# AD603_AGC.net
KiCad netlist of a schematic drawn in Altium Designer
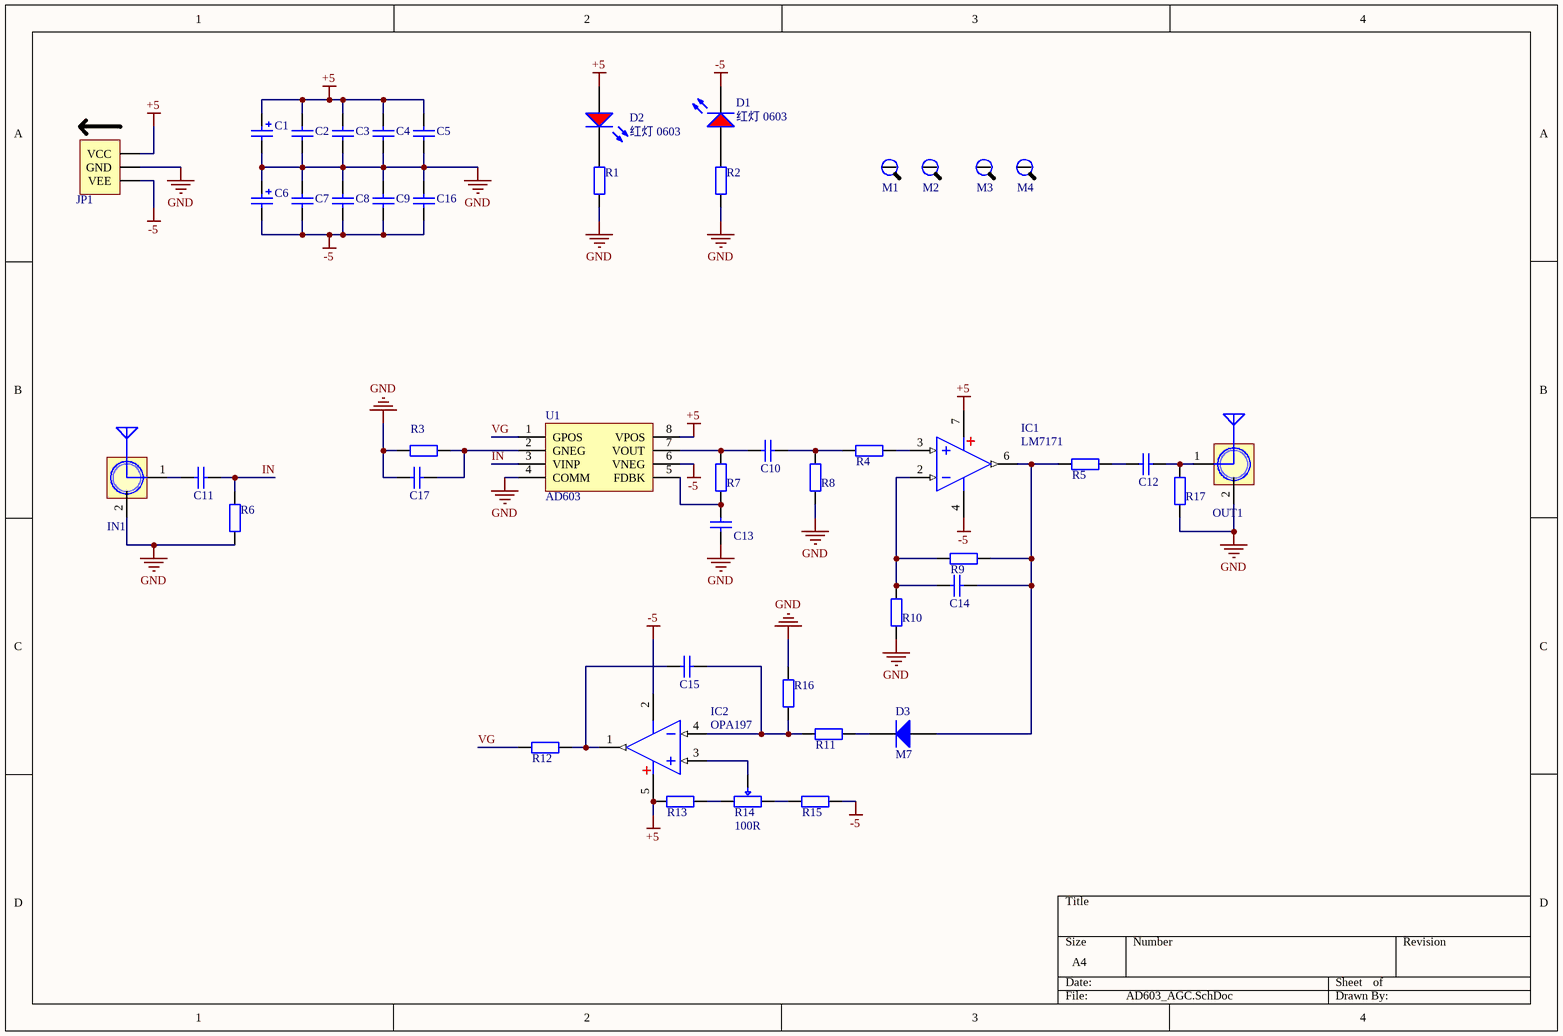
[diagram p0: AD603_AGC.SchDoc]

(export (version "E")
  (design (tool "Eeschema 10.0.6"))
  (components
    (comp (ref "C1")
      (value "10uF (106) ±10% 16V")
      (footprint "CASE-A_3216")
      (description "钽电容")
      (libsource (lib "JLC") (part "3216 10uF (106) 10% 16V"))
    )
    (comp (ref "C2")
      (value "100nF (104) 10% 50V")
      (footprint "0603_C")
      (description "贴片电容")
      (libsource (lib "JLC") (part "0603 100nF (104) 10% 50V"))
    )
    (comp (ref "C3")
      (value "100nF (104) 10% 50V")
      (footprint "0603_C")
      (description "贴片电容")
      (libsource (lib "JLC") (part "0603 100nF (104) 10% 50V"))
    )
    (comp (ref "C4")
      (value "100nF (104) 10% 50V")
      (footprint "0603_C")
      (description "贴片电容")
      (libsource (lib "JLC") (part "0603 100nF (104) 10% 50V"))
    )
    (comp (ref "C5")
      (value "100nF (104) 10% 50V")
      (footprint "0603_C")
      (description "贴片电容")
      (libsource (lib "JLC") (part "0603 100nF (104) 10% 50V"))
    )
    (comp (ref "C6")
      (value "10uF (106) ±10% 16V")
      (footprint "CASE-A_3216")
      (description "钽电容")
      (libsource (lib "JLC") (part "3216 10uF (106) 10% 16V"))
    )
    (comp (ref "C7")
      (value "100nF (104) 10% 50V")
      (footprint "0603_C")
      (description "贴片电容")
      (libsource (lib "JLC") (part "0603 100nF (104) 10% 50V"))
    )
    (comp (ref "C8")
      (value "100nF (104) 10% 50V")
      (footprint "0603_C")
      (description "贴片电容")
      (libsource (lib "JLC") (part "0603 100nF (104) 10% 50V"))
    )
    (comp (ref "C9")
      (value "100nF (104) 10% 50V")
      (footprint "0603_C")
      (description "贴片电容")
      (libsource (lib "JLC") (part "0603 100nF (104) 10% 50V"))
    )
    (comp (ref "C10")
      (value "100nF (104) 10% 50V")
      (footprint "0603_C")
      (description "贴片电容")
      (libsource (lib "JLC") (part "0603 100nF (104) 10% 50V"))
    )
    (comp (ref "C11")
      (value "100nF (104) 10% 50V")
      (footprint "0603_C")
      (description "贴片电容")
      (libsource (lib "JLC") (part "0603 100nF (104) 10% 50V"))
    )
    (comp (ref "C12")
      (value "100nF (104) 10% 50V")
      (footprint "0603_C")
      (description "贴片电容")
      (libsource (lib "JLC") (part "0603 100nF (104) 10% 50V"))
    )
    (comp (ref "C13")
      (value "100nF (104) 10% 50V")
      (footprint "0603_C")
      (description "贴片电容")
      (libsource (lib "JLC") (part "0603 100nF (104) 10% 50V"))
    )
    (comp (ref "C14")
      (value "100nF (104) 10% 50V")
      (footprint "0603_C")
      (description "贴片电容")
      (libsource (lib "JLC") (part "0603 100nF (104) 10% 50V"))
    )
    (comp (ref "C15")
      (value "100nF (104) 10% 50V")
      (footprint "0603_C")
      (description "贴片电容")
      (libsource (lib "JLC") (part "0603 100nF (104) 10% 50V"))
    )
    (comp (ref "C16")
      (value "100nF (104) 10% 50V")
      (footprint "0603_C")
      (description "贴片电容")
      (libsource (lib "JLC") (part "0603 100nF (104) 10% 50V"))
    )
    (comp (ref "C17")
      (value "100nF (104) 10% 50V")
      (footprint "0603_C")
      (description "贴片电容")
      (libsource (lib "JLC") (part "0603 100nF (104) 10% 50V"))
    )
    (comp (ref "D1")
      (value "红灯 0603")
      (footprint "0603_LED_S1")
      (description "发光二极管")
      (libsource (lib "JLC") (part "0603 红灯"))
    )
    (comp (ref "D2")
      (value "红灯 0603")
      (footprint "0603_LED_S1")
      (description "发光二极管")
      (libsource (lib "JLC") (part "0603 红灯"))
    )
    (comp (ref "D3")
      (value "M7")
      (footprint "SMA(DO-214AC)_S1")
      (description "二极管")
      (libsource (lib "JLC") (part "SMA(DO-214AC) M7"))
    )
    (comp (ref "IC1")
      (value "LM7171")
      (footprint "SOP8_N")
      (description "SOP8_轨至轨运放")
      (fields (field (name "版权归属") "源创客"))
      (libsource (lib "1.5   - 运放-功放") (part "SGM8521-8Pin"))
    )
    (comp (ref "IC2")
      (value "OPA197")
      (footprint "SOT23-5N")
      (description "SOT23-5_轨至轨运放")
      (fields (field (name "版权归属") "源创客"))
      (libsource (lib "1.5   - 运放-功放") (part "SGM8521-5Pin"))
    )
    (comp (ref "IN1")
      (value "SMA WIFI 天线接口")
      (footprint "SMA")
      (description "SMA-2.4G射频天线接口")
      (fields (field (name "版权归属") "源创客"))
      (libsource (lib "") (part "PORT_SMA_1"))
    )
    (comp (ref "JP1")
      (value "HDR-1X3")
      (footprint "Power_IN_3.81-3P")
      (description "3P接插件,模块双电源供电口")
      (fields (field (name "版权归属") "源创客"))
      (libsource (lib "Cooperation") (part "PORT_Power_IN3"))
    )
    (comp (ref "M1")
      (value "M3")
      (footprint "M3x10_L")
      (description "螺丝")
      (libsource (lib "Cooperation") (part "ELSE_M3_screw"))
    )
    (comp (ref "M2")
      (value "M3")
      (footprint "M3x10_L")
      (description "螺丝")
      (libsource (lib "Cooperation") (part "ELSE_M3_screw"))
    )
    (comp (ref "M3")
      (value "M3")
      (footprint "M3x10_L")
      (description "螺丝")
      (libsource (lib "Cooperation") (part "ELSE_M3_screw"))
    )
    (comp (ref "M4")
      (value "M3")
      (footprint "M3x10_L")
      (description "螺丝")
      (libsource (lib "Cooperation") (part "ELSE_M3_screw"))
    )
    (comp (ref "OUT1")
      (value "SMA WIFI 天线接口")
      (footprint "SMA")
      (description "SMA-2.4G射频天线接口")
      (fields (field (name "版权归属") "源创客"))
      (libsource (lib "Cooperation") (part "PORT_SMA"))
    )
    (comp (ref "R1")
      (value "10KΩ (1002) ±1%")
      (footprint "0603_R")
      (description "贴片电阻")
      (libsource (lib "") (part "0603 10KΩ (1002) 1%_1"))
    )
    (comp (ref "R2")
      (value "10KΩ (1002) ±1%")
      (footprint "0603_R")
      (description "贴片电阻")
      (libsource (lib "") (part "0603 10KΩ (1002) 1%_1"))
    )
    (comp (ref "R3")
      (value "10KΩ (1002) ±1%")
      (footprint "0603_R")
      (description "贴片电阻")
      (libsource (lib "") (part "0603 10KΩ (1002) 1%_3"))
    )
    (comp (ref "R4")
      (value "10KΩ (1002) ±1%")
      (footprint "0603_R")
      (description "贴片电阻")
      (libsource (lib "") (part "0603 10KΩ (1002) 1%_2"))
    )
    (comp (ref "R5")
      (value "10KΩ (1002) ±1%")
      (footprint "0603_R")
      (description "贴片电阻")
      (libsource (lib "") (part "0603 10KΩ (1002) 1%_2"))
    )
    (comp (ref "R6")
      (value "10KΩ (1002) ±1%")
      (footprint "0603_R")
      (description "贴片电阻")
      (libsource (lib "") (part "0603 10KΩ (1002) 1%_1"))
    )
    (comp (ref "R7")
      (value "10KΩ (1002) ±1%")
      (footprint "0603_R")
      (description "贴片电阻")
      (libsource (lib "JLC") (part "0603 10KΩ (1002) 1%"))
    )
    (comp (ref "R8")
      (value "10KΩ (1002) ±1%")
      (footprint "0603_R")
      (description "贴片电阻")
      (libsource (lib "JLC") (part "0603 10KΩ (1002) 1%"))
    )
    (comp (ref "R9")
      (value "10KΩ (1002) ±1%")
      (footprint "0603_R")
      (description "贴片电阻")
      (libsource (lib "") (part "0603 10KΩ (1002) 1%_2"))
    )
    (comp (ref "R10")
      (value "10KΩ (1002) ±1%")
      (footprint "0603_R")
      (description "贴片电阻")
      (libsource (lib "JLC") (part "0603 10KΩ (1002) 1%"))
    )
    (comp (ref "R11")
      (value "10KΩ (1002) ±1%")
      (footprint "0603_R")
      (description "贴片电阻")
      (libsource (lib "") (part "0603 10KΩ (1002) 1%_2"))
    )
    (comp (ref "R12")
      (value "10KΩ (1002) ±1%")
      (footprint "0603_R")
      (description "贴片电阻")
      (libsource (lib "") (part "0603 10KΩ (1002) 1%_2"))
    )
    (comp (ref "R13")
      (value "10KΩ (1002) ±1%")
      (footprint "0603_R")
      (description "贴片电阻")
      (libsource (lib "") (part "0603 10KΩ (1002) 1%_2"))
    )
    (comp (ref "R14")
      (value "100R")
      (footprint "adjustable resistor")
      (description "adjustable resistor可调电阻")
      (fields (field (name "Comment") "Ω"))
      (libsource (lib "Cooperation") (part "RES_Adjustable_Resistor"))
    )
    (comp (ref "R15")
      (value "10KΩ (1002) ±1%")
      (footprint "0603_R")
      (description "贴片电阻")
      (libsource (lib "") (part "0603 10KΩ (1002) 1%_2"))
    )
    (comp (ref "R16")
      (value "10KΩ (1002) ±1%")
      (footprint "0603_R")
      (description "贴片电阻")
      (libsource (lib "") (part "0603 10KΩ (1002) 1%_1"))
    )
    (comp (ref "R17")
      (value "10KΩ (1002) ±1%")
      (footprint "0603_R")
      (description "贴片电阻")
      (libsource (lib "") (part "0603 10KΩ (1002) 1%_1"))
    )
    (comp (ref "U1") (value "AD603") (footprint "SO-8") (libsource (lib "Cooperation") (part "AD603")))
  )
  (nets
    (net (code "1") (name "+5") (class "Default")
      (node (ref "C1") (pin "1") (pinfunction "1_1") (pintype "passive"))
      (node (ref "C2") (pin "2") (pinfunction "2_2") (pintype "passive"))
      (node (ref "C3") (pin "2") (pinfunction "2_2") (pintype "passive"))
      (node (ref "C4") (pin "2") (pinfunction "2_2") (pintype "passive"))
      (node (ref "C5") (pin "2") (pinfunction "2_2") (pintype "passive"))
      (node (ref "D2") (pin "A") (pinfunction "A_A") (pintype "passive"))
      (node (ref "IC1") (pin "7") (pinfunction "V+_7") (pintype "power_in"))
      (node (ref "IC2") (pin "5") (pinfunction "V+_5") (pintype "power_in"))
      (node (ref "JP1") (pin "1") (pinfunction "VCC_1") (pintype "passive"))
      (node (ref "R13") (pin "1") (pinfunction "1_1") (pintype "passive"))
      (node (ref "U1") (pin "8") (pinfunction "VPOS_8") (pintype "passive"))
    )
    (net (code "2") (name "-5") (class "Default")
      (node (ref "C16") (pin "1") (pinfunction "1_1") (pintype "passive"))
      (node (ref "C6") (pin "2") (pinfunction "2_2") (pintype "passive"))
      (node (ref "C7") (pin "1") (pinfunction "1_1") (pintype "passive"))
      (node (ref "C8") (pin "1") (pinfunction "1_1") (pintype "passive"))
      (node (ref "C9") (pin "1") (pinfunction "1_1") (pintype "passive"))
      (node (ref "D1") (pin "K") (pinfunction "K_K") (pintype "passive"))
      (node (ref "IC1") (pin "4") (pinfunction "V-_4") (pintype "power_in"))
      (node (ref "IC2") (pin "2") (pinfunction "V-_2") (pintype "power_in"))
      (node (ref "JP1") (pin "3") (pinfunction "VEE_3") (pintype "passive"))
      (node (ref "R15") (pin "2") (pinfunction "2_2") (pintype "passive"))
      (node (ref "U1") (pin "6") (pinfunction "VNEG_6") (pintype "passive"))
    )
    (net (code "3") (name "/IN") (class "Default")
      (node (ref "C11") (pin "1") (pinfunction "1_1") (pintype "passive"))
      (node (ref "R6") (pin "2") (pinfunction "2_2") (pintype "passive"))
      (node (ref "U1") (pin "3") (pinfunction "VINP_3") (pintype "passive"))
    )
    (net (code "4") (name "/VG") (class "Default")
      (node (ref "R12") (pin "1") (pinfunction "1_1") (pintype "passive"))
      (node (ref "U1") (pin "1") (pinfunction "GPOS_1") (pintype "passive"))
    )
    (net (code "5") (name "GND") (class "Default")
      (node (ref "C1") (pin "2") (pinfunction "2_2") (pintype "passive"))
      (node (ref "C13") (pin "2") (pinfunction "2_2") (pintype "passive"))
      (node (ref "C16") (pin "2") (pinfunction "2_2") (pintype "passive"))
      (node (ref "C17") (pin "2") (pinfunction "2_2") (pintype "passive"))
      (node (ref "C2") (pin "1") (pinfunction "1_1") (pintype "passive"))
      (node (ref "C3") (pin "1") (pinfunction "1_1") (pintype "passive"))
      (node (ref "C4") (pin "1") (pinfunction "1_1") (pintype "passive"))
      (node (ref "C5") (pin "1") (pinfunction "1_1") (pintype "passive"))
      (node (ref "C6") (pin "1") (pinfunction "1_1") (pintype "passive"))
      (node (ref "C7") (pin "2") (pinfunction "2_2") (pintype "passive"))
      (node (ref "C8") (pin "2") (pinfunction "2_2") (pintype "passive"))
      (node (ref "C9") (pin "2") (pinfunction "2_2") (pintype "passive"))
      (node (ref "IN1") (pin "2") (pinfunction "2_2") (pintype "passive"))
      (node (ref "JP1") (pin "2") (pinfunction "GND_2") (pintype "passive"))
      (node (ref "OUT1") (pin "2") (pinfunction "2_2") (pintype "passive"))
      (node (ref "R1") (pin "1") (pinfunction "1_1") (pintype "passive"))
      (node (ref "R10") (pin "2") (pinfunction "2_2") (pintype "passive"))
      (node (ref "R16") (pin "2") (pinfunction "2_2") (pintype "passive"))
      (node (ref "R17") (pin "1") (pinfunction "1_1") (pintype "passive"))
      (node (ref "R2") (pin "1") (pinfunction "1_1") (pintype "passive"))
      (node (ref "R3") (pin "2") (pinfunction "2_2") (pintype "passive"))
      (node (ref "R6") (pin "1") (pinfunction "1_1") (pintype "passive"))
      (node (ref "R8") (pin "2") (pinfunction "2_2") (pintype "passive"))
      (node (ref "U1") (pin "4") (pinfunction "COMM_4") (pintype "passive"))
    )
    (net (code "6") (name "Net-(C10-Pad1)") (class "Default")
      (node (ref "C10") (pin "1") (pinfunction "1_1") (pintype "passive"))
      (node (ref "R4") (pin "1") (pinfunction "1_1") (pintype "passive"))
      (node (ref "R8") (pin "1") (pinfunction "1_1") (pintype "passive"))
    )
    (net (code "7") (name "Net-(C12-Pad2)") (class "Default")
      (node (ref "C12") (pin "2") (pinfunction "2_2") (pintype "passive"))
      (node (ref "R5") (pin "2") (pinfunction "2_2") (pintype "passive"))
    )
    (net (code "8") (name "Net-(D1-PadA)") (class "Default")
      (node (ref "D1") (pin "A") (pinfunction "A_A") (pintype "passive"))
      (node (ref "R2") (pin "2") (pinfunction "2_2") (pintype "passive"))
    )
    (net (code "9") (name "Net-(D2-PadK)") (class "Default")
      (node (ref "D2") (pin "K") (pinfunction "K_K") (pintype "passive"))
      (node (ref "R1") (pin "2") (pinfunction "2_2") (pintype "passive"))
    )
    (net (code "10") (name "Net-(D3-A)") (class "Default")
      (node (ref "C14") (pin "1") (pinfunction "1_1") (pintype "passive"))
      (node (ref "D3") (pin "1") (pinfunction "A_1") (pintype "passive"))
      (node (ref "IC1") (pin "6") (pinfunction "OUT_6") (pintype "output"))
      (node (ref "R5") (pin "1") (pinfunction "1_1") (pintype "passive"))
      (node (ref "R9") (pin "2") (pinfunction "2_2") (pintype "passive"))
    )
    (net (code "11") (name "Net-(D3-K)") (class "Default")
      (node (ref "D3") (pin "2") (pinfunction "K_2") (pintype "passive"))
      (node (ref "R11") (pin "2") (pinfunction "2_2") (pintype "passive"))
    )
    (net (code "12") (name "Net-(IC1-IN-)") (class "Default")
      (node (ref "C14") (pin "2") (pinfunction "2_2") (pintype "passive"))
      (node (ref "IC1") (pin "2") (pinfunction "IN-_2") (pintype "input"))
      (node (ref "R10") (pin "1") (pinfunction "1_1") (pintype "passive"))
      (node (ref "R9") (pin "1") (pinfunction "1_1") (pintype "passive"))
    )
    (net (code "13") (name "Net-(IC1-Pad3)") (class "Default")
      (node (ref "IC1") (pin "3") (pinfunction "3_3") (pintype "input"))
      (node (ref "R4") (pin "2") (pinfunction "2_2") (pintype "passive"))
    )
    (net (code "14") (name "Net-(IC2-IN+)") (class "Default")
      (node (ref "IC2") (pin "3") (pinfunction "IN+_3") (pintype "input"))
      (node (ref "R14") (pin "2") (pinfunction "2_2") (pintype "passive"))
    )
    (net (code "15") (name "Net-(IC2-IN-)") (class "Default")
      (node (ref "C15") (pin "1") (pinfunction "1_1") (pintype "passive"))
      (node (ref "IC2") (pin "4") (pinfunction "IN-_4") (pintype "input"))
      (node (ref "R11") (pin "1") (pinfunction "1_1") (pintype "passive"))
      (node (ref "R16") (pin "1") (pinfunction "1_1") (pintype "passive"))
    )
    (net (code "16") (name "Net-(IC2-OUT)") (class "Default")
      (node (ref "C15") (pin "2") (pinfunction "2_2") (pintype "passive"))
      (node (ref "IC2") (pin "1") (pinfunction "OUT_1") (pintype "output"))
      (node (ref "R12") (pin "2") (pinfunction "2_2") (pintype "passive"))
    )
    (net (code "17") (name "Net-(IN1-SINGLE)") (class "Default")
      (node (ref "C11") (pin "2") (pinfunction "2_2") (pintype "passive"))
      (node (ref "IN1") (pin "1") (pinfunction "SINGLE_1") (pintype "passive"))
    )
    (net (code "18") (name "Net-(OUT1-SINGLE)") (class "Default")
      (node (ref "C12") (pin "1") (pinfunction "1_1") (pintype "passive"))
      (node (ref "OUT1") (pin "1") (pinfunction "SINGLE_1") (pintype "passive"))
      (node (ref "R17") (pin "2") (pinfunction "2_2") (pintype "passive"))
    )
    (net (code "19") (name "Net-(R13-Pad2)") (class "Default")
      (node (ref "R13") (pin "2") (pinfunction "2_2") (pintype "passive"))
      (node (ref "R14") (pin "1") (pinfunction "1_1") (pintype "passive"))
    )
    (net (code "20") (name "Net-(R14-Pad3)") (class "Default")
      (node (ref "R14") (pin "3") (pinfunction "3_3") (pintype "passive"))
      (node (ref "R15") (pin "1") (pinfunction "1_1") (pintype "passive"))
    )
    (net (code "21") (name "Net-(U1-FDBK)") (class "Default")
      (node (ref "C13") (pin "1") (pinfunction "1_1") (pintype "passive"))
      (node (ref "R7") (pin "2") (pinfunction "2_2") (pintype "passive"))
      (node (ref "U1") (pin "5") (pinfunction "FDBK_5") (pintype "passive"))
    )
    (net (code "22") (name "Net-(U1-GNEG)") (class "Default")
      (node (ref "C17") (pin "1") (pinfunction "1_1") (pintype "passive"))
      (node (ref "R3") (pin "1") (pinfunction "1_1") (pintype "passive"))
      (node (ref "U1") (pin "2") (pinfunction "GNEG_2") (pintype "passive"))
    )
    (net (code "23") (name "Net-(U1-VOUT)") (class "Default")
      (node (ref "C10") (pin "2") (pinfunction "2_2") (pintype "passive"))
      (node (ref "R7") (pin "1") (pinfunction "1_1") (pintype "passive"))
      (node (ref "U1") (pin "7") (pinfunction "VOUT_7") (pintype "passive"))
    )
    (net (code "24") (name "unconnected-(M1-Pad1)") (class "Default")
      (node (ref "M1") (pin "1") (pinfunction "1_1") (pintype "passive"))
    )
    (net (code "25") (name "unconnected-(M2-Pad1)") (class "Default")
      (node (ref "M2") (pin "1") (pinfunction "1_1") (pintype "passive"))
    )
    (net (code "26") (name "unconnected-(M3-Pad1)") (class "Default")
      (node (ref "M3") (pin "1") (pinfunction "1_1") (pintype "passive"))
    )
    (net (code "27") (name "unconnected-(M4-Pad1)") (class "Default")
      (node (ref "M4") (pin "1") (pinfunction "1_1") (pintype "passive"))
    )
  )
)
